# power.net
KiCad netlist of a schematic drawn in EAGLE
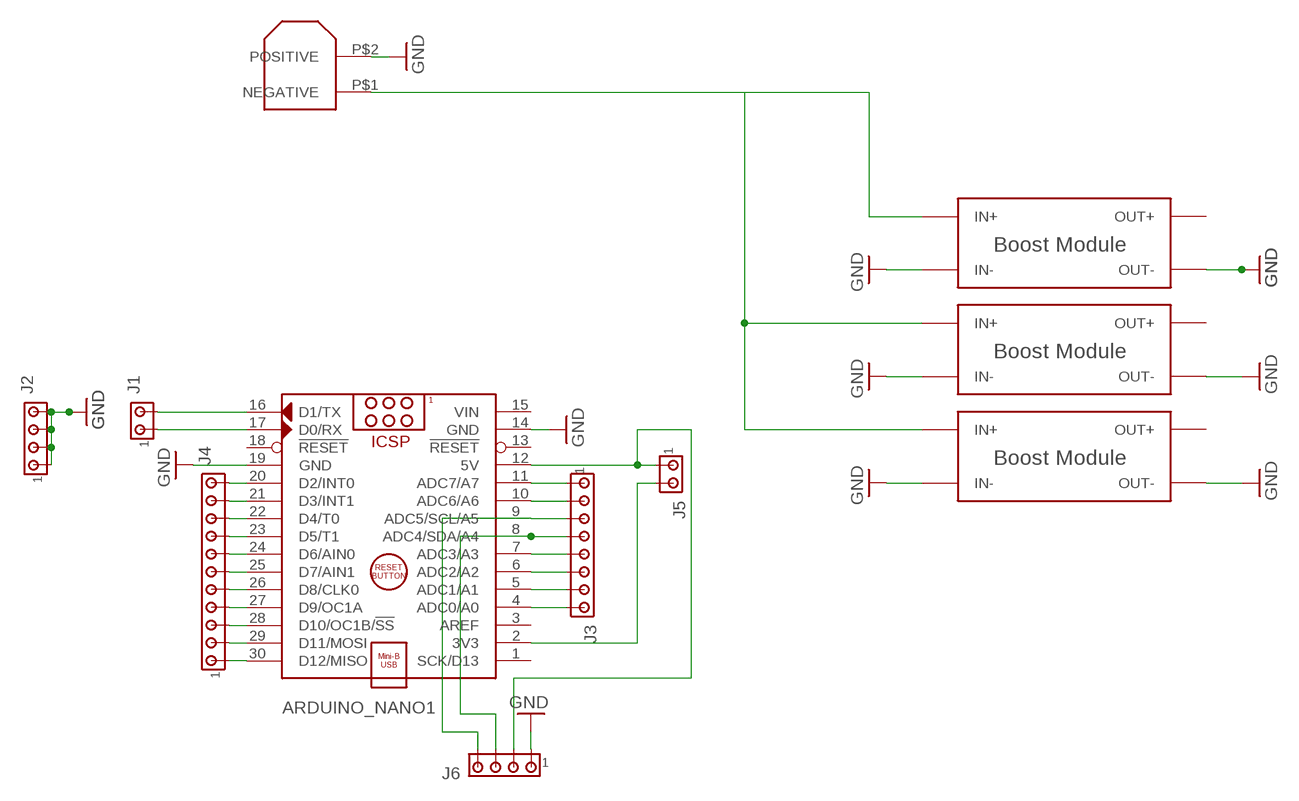
[diagram p0: schematic, sheet 1]

(export (version "E")
  (design (tool "Eeschema 10.0.6"))
  (components
    (comp (ref "ARDUINO_NANO1")
      (value "ARDUINO_NANO")
      (footprint "eagle-import:ARDUINO_NANO")
      (libsource (lib "eagle-import") (part "ARDUINO_NANO"))
    )
    (comp (ref "J1")
      (value "MTA02-100")
      (footprint "eagle-import:10X02MTA")
      (libsource (lib "eagle-import") (part "MTA02-100"))
    )
    (comp (ref "J2")
      (value "MTA04-100")
      (footprint "eagle-import:10X04MTA")
      (libsource (lib "eagle-import") (part "MTA04-100"))
    )
    (comp (ref "J3")
      (value "MTA08-100")
      (footprint "eagle-import:10X08MTA")
      (libsource (lib "eagle-import") (part "MTA08-100"))
    )
    (comp (ref "J4")
      (value "MTA11-156")
      (footprint "eagle-import:1X11MTA")
      (libsource (lib "eagle-import") (part "MTA11-156"))
    )
    (comp (ref "J5")
      (value "MTA02-100")
      (footprint "eagle-import:10X02MTA")
      (libsource (lib "eagle-import") (part "MTA02-100"))
    )
    (comp (ref "J6")
      (value "MTA04-100")
      (footprint "eagle-import:10X04MTA")
      (libsource (lib "eagle-import") (part "MTA04-100"))
    )
    (comp (ref "U$1")
      (value "BOOST_MODULE")
      (footprint "eagle-import:BOOST_MODULE")
      (libsource (lib "eagle-import") (part "BOOST_MODULE"))
    )
    (comp (ref "U$2")
      (value "BOOST_MODULE")
      (footprint "eagle-import:BOOST_MODULE")
      (libsource (lib "eagle-import") (part "BOOST_MODULE"))
    )
    (comp (ref "U$3")
      (value "BOOST_MODULE")
      (footprint "eagle-import:BOOST_MODULE")
      (libsource (lib "eagle-import") (part "BOOST_MODULE"))
    )
    (comp (ref "U$4")
      (value "XT60")
      (footprint "eagle-import:CONNECTOR")
      (libsource (lib "eagle-import") (part "XT60"))
    )
  )
  (nets
    (net (code "1") (name "/VIN") (class "Default")
      (node (ref "ARDUINO_NANO1") (pin "15") (pinfunction "VIN_15") (pintype "power_in"))
    )
    (net (code "2") (name "GND") (class "Default")
      (node (ref "ARDUINO_NANO1") (pin "14") (pinfunction "GND_14") (pintype "power_in"))
      (node (ref "ARDUINO_NANO1") (pin "19") (pinfunction "GND_19") (pintype "power_in"))
      (node (ref "J2") (pin "1") (pinfunction "1_1") (pintype "passive"))
      (node (ref "J2") (pin "2") (pinfunction "2_2") (pintype "passive"))
      (node (ref "J2") (pin "3") (pinfunction "3_3") (pintype "passive"))
      (node (ref "J2") (pin "4") (pinfunction "4_4") (pintype "passive"))
      (node (ref "J6") (pin "1") (pinfunction "1_1") (pintype "passive"))
      (node (ref "U$1") (pin "IN-") (pinfunction "IN-_IN-") (pintype "bidirectional"))
      (node (ref "U$1") (pin "OUT-") (pinfunction "OUT-_OUT-") (pintype "bidirectional"))
      (node (ref "U$2") (pin "IN-") (pinfunction "IN-_IN-") (pintype "bidirectional"))
      (node (ref "U$2") (pin "OUT-") (pinfunction "OUT-_OUT-") (pintype "bidirectional"))
      (node (ref "U$3") (pin "IN-") (pinfunction "IN-_IN-") (pintype "bidirectional"))
      (node (ref "U$3") (pin "OUT-") (pinfunction "OUT-_OUT-") (pintype "bidirectional"))
      (node (ref "U$4") (pin "P$2") (pinfunction "POSITIVE_P$2") (pintype "bidirectional"))
    )
    (net (code "3") (name "Net-(ARDUINO_NANO1-3V3)") (class "Default")
      (node (ref "ARDUINO_NANO1") (pin "2") (pinfunction "3V3_2") (pintype "output"))
      (node (ref "J5") (pin "2") (pinfunction "2_2") (pintype "passive"))
    )
    (net (code "4") (name "Net-(ARDUINO_NANO1-5V)") (class "Default")
      (node (ref "ARDUINO_NANO1") (pin "12") (pinfunction "5V_12") (pintype "power_in"))
      (node (ref "J5") (pin "1") (pinfunction "1_1") (pintype "passive"))
      (node (ref "J6") (pin "2") (pinfunction "2_2") (pintype "passive"))
    )
    (net (code "5") (name "Net-(ARDUINO_NANO1-ADC0{slash}A0)") (class "Default")
      (node (ref "ARDUINO_NANO1") (pin "4") (pinfunction "ADC0/A0_4") (pintype "bidirectional"))
      (node (ref "J3") (pin "8") (pinfunction "8_8") (pintype "passive"))
    )
    (net (code "6") (name "Net-(ARDUINO_NANO1-ADC1{slash}A1)") (class "Default")
      (node (ref "ARDUINO_NANO1") (pin "5") (pinfunction "ADC1/A1_5") (pintype "bidirectional"))
      (node (ref "J3") (pin "7") (pinfunction "7_7") (pintype "passive"))
    )
    (net (code "7") (name "Net-(ARDUINO_NANO1-ADC2{slash}A2)") (class "Default")
      (node (ref "ARDUINO_NANO1") (pin "6") (pinfunction "ADC2/A2_6") (pintype "bidirectional"))
      (node (ref "J3") (pin "6") (pinfunction "6_6") (pintype "passive"))
    )
    (net (code "8") (name "Net-(ARDUINO_NANO1-ADC3{slash}A3)") (class "Default")
      (node (ref "ARDUINO_NANO1") (pin "7") (pinfunction "ADC3/A3_7") (pintype "bidirectional"))
      (node (ref "J3") (pin "5") (pinfunction "5_5") (pintype "passive"))
    )
    (net (code "9") (name "Net-(ARDUINO_NANO1-ADC4{slash}SDA{slash}A4)") (class "Default")
      (node (ref "ARDUINO_NANO1") (pin "8") (pinfunction "ADC4/SDA/A4_8") (pintype "bidirectional"))
      (node (ref "J3") (pin "4") (pinfunction "4_4") (pintype "passive"))
      (node (ref "J6") (pin "3") (pinfunction "3_3") (pintype "passive"))
    )
    (net (code "10") (name "Net-(ARDUINO_NANO1-ADC5{slash}SCL{slash}A5)") (class "Default")
      (node (ref "ARDUINO_NANO1") (pin "9") (pinfunction "ADC5/SCL/A5_9") (pintype "bidirectional"))
      (node (ref "J3") (pin "3") (pinfunction "3_3") (pintype "passive"))
      (node (ref "J6") (pin "4") (pinfunction "4_4") (pintype "passive"))
    )
    (net (code "11") (name "Net-(ARDUINO_NANO1-ADC6{slash}A6)") (class "Default")
      (node (ref "ARDUINO_NANO1") (pin "10") (pinfunction "ADC6/A6_10") (pintype "bidirectional"))
      (node (ref "J3") (pin "2") (pinfunction "2_2") (pintype "passive"))
    )
    (net (code "12") (name "Net-(ARDUINO_NANO1-ADC7{slash}A7)") (class "Default")
      (node (ref "ARDUINO_NANO1") (pin "11") (pinfunction "ADC7/A7_11") (pintype "bidirectional"))
      (node (ref "J3") (pin "1") (pinfunction "1_1") (pintype "passive"))
    )
    (net (code "13") (name "Net-(ARDUINO_NANO1-D0{slash}RX)") (class "Default")
      (node (ref "ARDUINO_NANO1") (pin "17") (pinfunction "D0/RX_17") (pintype "bidirectional"))
      (node (ref "J1") (pin "1") (pinfunction "1_1") (pintype "passive"))
    )
    (net (code "14") (name "Net-(ARDUINO_NANO1-D1{slash}TX)") (class "Default")
      (node (ref "ARDUINO_NANO1") (pin "16") (pinfunction "D1/TX_16") (pintype "bidirectional"))
      (node (ref "J1") (pin "2") (pinfunction "2_2") (pintype "passive"))
    )
    (net (code "15") (name "Net-(ARDUINO_NANO1-D2{slash}INT0)") (class "Default")
      (node (ref "ARDUINO_NANO1") (pin "20") (pinfunction "D2/INT0_20") (pintype "bidirectional"))
      (node (ref "J4") (pin "11") (pinfunction "11_11") (pintype "passive"))
    )
    (net (code "16") (name "Net-(ARDUINO_NANO1-D3{slash}INT1)") (class "Default")
      (node (ref "ARDUINO_NANO1") (pin "21") (pinfunction "D3/INT1_21") (pintype "bidirectional"))
      (node (ref "J4") (pin "10") (pinfunction "10_10") (pintype "passive"))
    )
    (net (code "17") (name "Net-(ARDUINO_NANO1-D4{slash}T0)") (class "Default")
      (node (ref "ARDUINO_NANO1") (pin "22") (pinfunction "D4/T0_22") (pintype "bidirectional"))
      (node (ref "J4") (pin "9") (pinfunction "9_9") (pintype "passive"))
    )
    (net (code "18") (name "Net-(ARDUINO_NANO1-D5{slash}T1)") (class "Default")
      (node (ref "ARDUINO_NANO1") (pin "23") (pinfunction "D5/T1_23") (pintype "bidirectional"))
      (node (ref "J4") (pin "8") (pinfunction "8_8") (pintype "passive"))
    )
    (net (code "19") (name "Net-(ARDUINO_NANO1-D6{slash}AIN0)") (class "Default")
      (node (ref "ARDUINO_NANO1") (pin "24") (pinfunction "D6/AIN0_24") (pintype "bidirectional"))
      (node (ref "J4") (pin "7") (pinfunction "7_7") (pintype "passive"))
    )
    (net (code "20") (name "Net-(ARDUINO_NANO1-D7{slash}AIN1)") (class "Default")
      (node (ref "ARDUINO_NANO1") (pin "25") (pinfunction "D7/AIN1_25") (pintype "bidirectional"))
      (node (ref "J4") (pin "6") (pinfunction "6_6") (pintype "passive"))
    )
    (net (code "21") (name "Net-(ARDUINO_NANO1-D8{slash}CLK0)") (class "Default")
      (node (ref "ARDUINO_NANO1") (pin "26") (pinfunction "D8/CLK0_26") (pintype "bidirectional"))
      (node (ref "J4") (pin "5") (pinfunction "5_5") (pintype "passive"))
    )
    (net (code "22") (name "Net-(ARDUINO_NANO1-D9{slash}OC1A)") (class "Default")
      (node (ref "ARDUINO_NANO1") (pin "27") (pinfunction "D9/OC1A_27") (pintype "bidirectional"))
      (node (ref "J4") (pin "4") (pinfunction "4_4") (pintype "passive"))
    )
    (net (code "23") (name "Net-(ARDUINO_NANO1-D10{slash}OC1B{slash}~{SS})") (class "Default")
      (node (ref "ARDUINO_NANO1") (pin "28") (pinfunction "D10/OC1B/~{SS}_28") (pintype "bidirectional"))
      (node (ref "J4") (pin "3") (pinfunction "3_3") (pintype "passive"))
    )
    (net (code "24") (name "Net-(ARDUINO_NANO1-D11{slash}MOSI)") (class "Default")
      (node (ref "ARDUINO_NANO1") (pin "29") (pinfunction "D11/MOSI_29") (pintype "bidirectional"))
      (node (ref "J4") (pin "2") (pinfunction "2_2") (pintype "passive"))
    )
    (net (code "25") (name "Net-(ARDUINO_NANO1-D12{slash}MISO)") (class "Default")
      (node (ref "ARDUINO_NANO1") (pin "30") (pinfunction "D12/MISO_30") (pintype "bidirectional"))
      (node (ref "J4") (pin "1") (pinfunction "1_1") (pintype "passive"))
    )
    (net (code "26") (name "Net-(U$4-NEGATIVE)") (class "Default")
      (node (ref "U$1") (pin "IN+") (pinfunction "IN+_IN+") (pintype "bidirectional"))
      (node (ref "U$2") (pin "IN+") (pinfunction "IN+_IN+") (pintype "bidirectional"))
      (node (ref "U$3") (pin "IN+") (pinfunction "IN+_IN+") (pintype "bidirectional"))
      (node (ref "U$4") (pin "P$1") (pinfunction "NEGATIVE_P$1") (pintype "bidirectional"))
    )
    (net (code "27") (name "unconnected-(ARDUINO_NANO1-AREF-Pad3)") (class "Default")
      (node (ref "ARDUINO_NANO1") (pin "3") (pinfunction "AREF_3") (pintype "input"))
    )
    (net (code "28") (name "unconnected-(ARDUINO_NANO1-SCK{slash}D13-Pad1)") (class "Default")
      (node (ref "ARDUINO_NANO1") (pin "1") (pinfunction "SCK/D13_1") (pintype "bidirectional"))
    )
    (net (code "29") (name "unconnected-(ARDUINO_NANO1-~{RESET}-Pad13)") (class "Default")
      (node (ref "ARDUINO_NANO1") (pin "13") (pinfunction "~{RESET}_13") (pintype "input"))
    )
    (net (code "30") (name "unconnected-(ARDUINO_NANO1-~{RESET}-Pad18)") (class "Default")
      (node (ref "ARDUINO_NANO1") (pin "18") (pinfunction "~{RESET}_18") (pintype "input"))
    )
    (net (code "31") (name "unconnected-(U$1-PadOUT+)") (class "Default")
      (node (ref "U$1") (pin "OUT+") (pinfunction "OUT+_OUT+") (pintype "bidirectional"))
    )
    (net (code "32") (name "unconnected-(U$2-PadOUT+)") (class "Default")
      (node (ref "U$2") (pin "OUT+") (pinfunction "OUT+_OUT+") (pintype "bidirectional"))
    )
    (net (code "33") (name "unconnected-(U$3-PadOUT+)") (class "Default")
      (node (ref "U$3") (pin "OUT+") (pinfunction "OUT+_OUT+") (pintype "bidirectional"))
    )
  )
)
